# Switch_Line_of_One_DC_Pin.net
KiCad netlist of a schematic drawn in Altium Designer
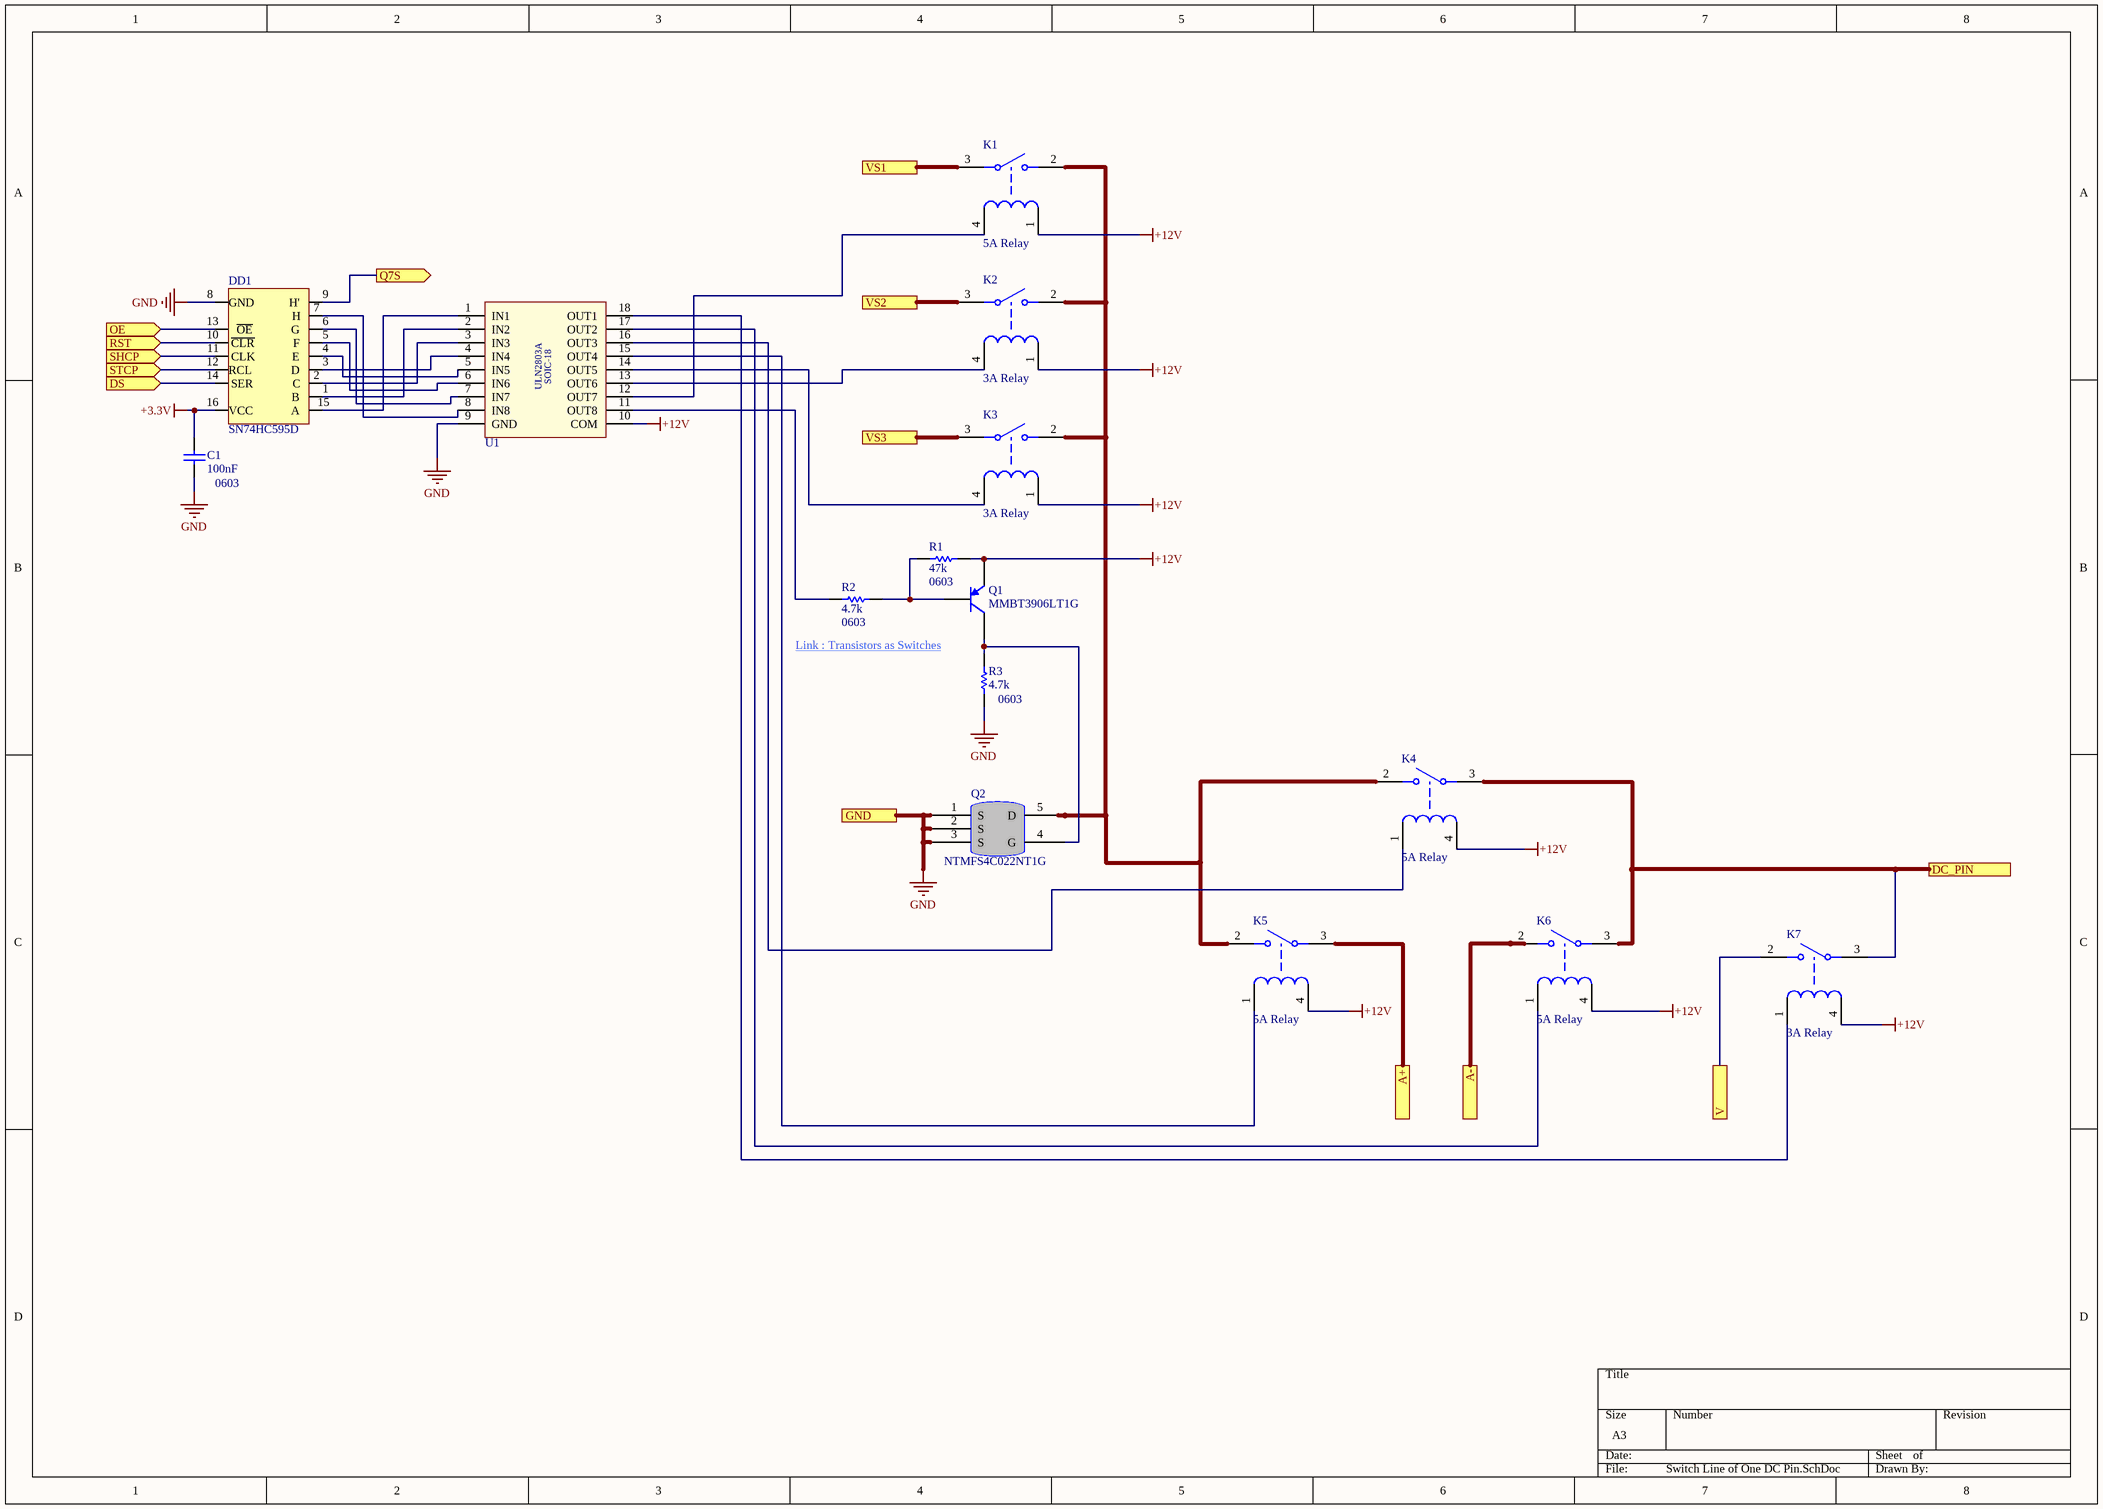
[diagram p0: Switch Line of One DC Pin.SchDoc]

(export (version "E")
  (design (tool "Eeschema 10.0.6"))
  (components
    (comp (ref "C1")
      (value "100nF")
      (footprint "CAPC1608X09N")
      (description "0603 10 nF 50 V ± 10% Tolerance X7R Surface Mount Multilayer Ceramic Capacitor")
      (fields
        (field (name "MANUFACTURE PART NUMBER") "CC0603KRX7R9BB104")
        (field (name "MANUFACTURER") "YAGEO")
        (field (name "PACKAGE / CASE") "0603")
      )
      (libsource (lib "DC Switch Matrix") (part "CMP-2f55e5122ad9f092-5"))
    )
    (comp (ref "DD1")
      (value "SN74HC595D")
      (footprint "PCB-72k1vk0k27b6qyyenbg0-1")
      (description "Shift Register Single 8-Bit Serial to Serial/Parallel 16-Pin SOIC Tube")
      (fields
        (field (name "MANUFACTURE PART NUMBER") "74HC595D,118")
        (field (name "MANUFACTURER") "Nexperia")
      )
      (libsource (lib "DC Switch Matrix") (part "CMP-ded317d957220114-5"))
    )
    (comp (ref "K1")
      (value "5A Relay")
      (footprint "PCB-ei6nokn2irsc2a7yt94x-1")
      (description "General Purpose Non Latching 12VDC SPST-NO 5A Through Hole Relays RoHS")
      (fields
        (field (name "MANUFACTURER") "HF(Xiamen Hongfa Electroacoustic)")
        (field (name "MANUFACTURE PART NUMBER") "HF46F/12-HS1")
      )
      (libsource (lib "DC Switch Matrix") (part "CMP-edc624afa9603201-3"))
    )
    (comp (ref "K2")
      (value "3A Relay")
      (footprint "PCB-ei6nokn2irsc2a7yt94x-1")
      (description "Power Relay 12VDC 3DC/5AAC SPST-NO( (20.5mm 7.2mm 15.3mm)) THT")
      (fields
        (field (name "MANUFACTURER") "Omron Electronics")
        (field (name "MANUFACTURE PART NUMBER") "G5NB-1A-E-DC12")
      )
      (libsource (lib "DC Switch Matrix") (part "CMP-edc624afa9603201-3"))
    )
    (comp (ref "K3")
      (value "3A Relay")
      (footprint "PCB-ei6nokn2irsc2a7yt94x-1")
      (description "Power Relay 12VDC 3DC/5AAC SPST-NO( (20.5mm 7.2mm 15.3mm)) THT")
      (fields
        (field (name "MANUFACTURER") "Omron Electronics")
        (field (name "MANUFACTURE PART NUMBER") "G5NB-1A-E-DC12")
      )
      (libsource (lib "DC Switch Matrix") (part "CMP-edc624afa9603201-3"))
    )
    (comp (ref "K4")
      (value "5A Relay")
      (footprint "PCB-ei6nokn2irsc2a7yt94x-1")
      (description "General Purpose Non Latching 12VDC SPST-NO 5A Through Hole Relays RoHS")
      (fields
        (field (name "MANUFACTURER") "HF(Xiamen Hongfa Electroacoustic)")
        (field (name "MANUFACTURE PART NUMBER") "HF46F/12-HS1")
      )
      (libsource (lib "") (part "CMP-edc624afa9603201-3_1"))
    )
    (comp (ref "K5")
      (value "5A Relay")
      (footprint "PCB-ei6nokn2irsc2a7yt94x-1")
      (description "General Purpose Non Latching 12VDC SPST-NO 5A Through Hole Relays RoHS")
      (fields
        (field (name "MANUFACTURER") "HF(Xiamen Hongfa Electroacoustic)")
        (field (name "MANUFACTURE PART NUMBER") "HF46F/12-HS1")
      )
      (libsource (lib "") (part "CMP-edc624afa9603201-3_1"))
    )
    (comp (ref "K6")
      (value "5A Relay")
      (footprint "PCB-ei6nokn2irsc2a7yt94x-1")
      (description "General Purpose Non Latching 12VDC SPST-NO 5A Through Hole Relays RoHS")
      (fields
        (field (name "MANUFACTURER") "HF(Xiamen Hongfa Electroacoustic)")
        (field (name "MANUFACTURE PART NUMBER") "HF46F/12-HS1")
      )
      (libsource (lib "") (part "CMP-edc624afa9603201-3_1"))
    )
    (comp (ref "K7")
      (value "3A Relay")
      (footprint "PCB-ei6nokn2irsc2a7yt94x-1")
      (description "Power Relay 12VDC 3DC/5AAC SPST-NO( (20.5mm 7.2mm 15.3mm)) THT")
      (fields
        (field (name "MANUFACTURER") "Omron Electronics")
        (field (name "MANUFACTURE PART NUMBER") "G5NB-1A-E-DC12")
      )
      (libsource (lib "") (part "CMP-edc624afa9603201-3_1"))
    )
    (comp (ref "Q1")
      (value "MMBT3906LT1G")
      (footprint "SOT-23")
      (description "Bipolar (BJT) Single Transistor, General Purpose, PNP, -40 V, 250 MHz, 225 mW, -200 mA, 300")
      (fields (field (name "MANUFACTURER") "ON Semiconductor"))
      (libsource (lib "DC Switch Matrix") (part "CMP-857798-9"))
    )
    (comp (ref "Q2")
      (value "NTMFS4C022NT1G")
      (footprint "PCB-iok221h7g3hg093tnixb-1")
      (description "Power MOSFET 30V 136A 1.7 mOhm Single N?Channel SO?8FL")
      (fields (field (name "MANUFACTURER") "ON Semiconductor"))
      (libsource (lib "DC Switch Matrix") (part "CMP-42ac8f2778579d6b-1"))
    )
    (comp (ref "R1")
      (value "47k")
      (footprint "gen0603-2")
      (description "Surface Mount Thick Film Resistor, RC Series, 1 kohm, 100 mW, - 1%, 50 V, 0603 [1608 Metric]")
      (fields
        (field (name "MANUFACTURER") "UNI-ROYAL(Uniroyal Elec)")
        (field (name "MANUFACTURE PART NUMBER") "0603WAF4702T5E")
        (field (name "PACKAGE / CASE") "0603")
      )
      (libsource (lib "DC Switch Matrix") (part "CMP-1853278-27"))
    )
    (comp (ref "R2")
      (value "4.7k")
      (footprint "gen0603-2")
      (description "Surface Mount Thick Film Resistor, RC Series, 1 kohm, 100 mW, - 1%, 50 V, 0603 [1608 Metric]")
      (fields
        (field (name "MANUFACTURER") "YAGEO")
        (field (name "MANUFACTURE PART NUMBER") "RC0603FR-074K7L")
        (field (name "PACKAGE / CASE") "0603")
      )
      (libsource (lib "DC Switch Matrix") (part "CMP-1853278-27"))
    )
    (comp (ref "R3")
      (value "4.7k")
      (footprint "gen0603-2")
      (description "Surface Mount Thick Film Resistor, RC Series, 1 kohm, 100 mW, - 1%, 50 V, 0603 [1608 Metric]")
      (fields
        (field (name "MANUFACTURER") "YAGEO")
        (field (name "MANUFACTURE PART NUMBER") "RC0603FR-074K7L")
        (field (name "PACKAGE / CASE") "0603")
      )
      (libsource (lib "DC Switch Matrix") (part "CMP-1853278-27"))
    )
    (comp (ref "U1")
      (value "ULN2803A (SOIC-18)")
      (footprint "PCB-gcdku7p92m9mz9ih2yin-1")
      (description "Bipolar (BJT) Array Transistor, Darlington, NPN, 50 V, 500 mA, SOIC")
      (fields (field (name "MANUFACTURE PART NUMBER") "ULN2803A") (field (name "MANUFACTURER") "Mixic"))
      (libsource (lib "DC Switch Matrix") (part "CMP-19353911-22"))
    )
  )
  (nets
    (net (code "1") (name "+3.3V") (class "Default")
      (node (ref "C1") (pin "2") (pinfunction "2_2") (pintype "passive"))
      (node (ref "DD1") (pin "16") (pinfunction "VCC_16") (pintype "passive"))
    )
    (net (code "2") (name "+12V") (class "Default")
      (node (ref "K1") (pin "1") (pinfunction "1_1") (pintype "passive"))
      (node (ref "K2") (pin "1") (pinfunction "1_1") (pintype "passive"))
      (node (ref "K3") (pin "1") (pinfunction "1_1") (pintype "passive"))
      (node (ref "K4") (pin "4") (pinfunction "4_4") (pintype "passive"))
      (node (ref "K5") (pin "4") (pinfunction "4_4") (pintype "passive"))
      (node (ref "K6") (pin "4") (pinfunction "4_4") (pintype "passive"))
      (node (ref "K7") (pin "4") (pinfunction "4_4") (pintype "passive"))
      (node (ref "Q1") (pin "2") (pinfunction "E_2") (pintype "passive"))
      (node (ref "R1") (pin "1") (pinfunction "1_1") (pintype "passive"))
      (node (ref "U1") (pin "10") (pinfunction "COM_10") (pintype "power_in"))
    )
    (net (code "3") (name "/A+") (class "Default")
      (node (ref "K5") (pin "3") (pinfunction "3_3") (pintype "passive"))
    )
    (net (code "4") (name "/A-") (class "Default")
      (node (ref "K6") (pin "2") (pinfunction "2_2") (pintype "passive"))
    )
    (net (code "5") (name "/DC_PIN") (class "Default")
      (node (ref "K4") (pin "3") (pinfunction "3_3") (pintype "passive"))
      (node (ref "K6") (pin "3") (pinfunction "3_3") (pintype "passive"))
      (node (ref "K7") (pin "3") (pinfunction "3_3") (pintype "passive"))
    )
    (net (code "6") (name "/DS") (class "Default")
      (node (ref "DD1") (pin "14") (pinfunction "SER_14") (pintype "passive"))
    )
    (net (code "7") (name "/OE") (class "Default")
      (node (ref "DD1") (pin "13") (pinfunction "~{OE}_13") (pintype "passive"))
    )
    (net (code "8") (name "/Q7S") (class "Default")
      (node (ref "DD1") (pin "9") (pinfunction "H'_9") (pintype "passive"))
    )
    (net (code "9") (name "/RST") (class "Default")
      (node (ref "DD1") (pin "10") (pinfunction "~{CLR}_10") (pintype "passive"))
    )
    (net (code "10") (name "/SHCP") (class "Default")
      (node (ref "DD1") (pin "11") (pinfunction "CLK_11") (pintype "passive"))
    )
    (net (code "11") (name "/STCP") (class "Default")
      (node (ref "DD1") (pin "12") (pinfunction "RCL_12") (pintype "passive"))
    )
    (net (code "12") (name "/V") (class "Default")
      (node (ref "K7") (pin "2") (pinfunction "2_2") (pintype "passive"))
    )
    (net (code "13") (name "/VS1") (class "Default")
      (node (ref "K1") (pin "3") (pinfunction "3_3") (pintype "passive"))
    )
    (net (code "14") (name "/VS2") (class "Default")
      (node (ref "K2") (pin "3") (pinfunction "3_3") (pintype "passive"))
    )
    (net (code "15") (name "/VS3") (class "Default")
      (node (ref "K3") (pin "3") (pinfunction "3_3") (pintype "passive"))
    )
    (net (code "16") (name "GND") (class "Default")
      (node (ref "C1") (pin "1") (pinfunction "1_1") (pintype "passive"))
      (node (ref "DD1") (pin "8") (pinfunction "GND_8") (pintype "passive"))
      (node (ref "Q2") (pin "1") (pinfunction "S_1") (pintype "passive"))
      (node (ref "Q2") (pin "2") (pinfunction "S_2") (pintype "passive"))
      (node (ref "Q2") (pin "3") (pinfunction "S_3") (pintype "passive"))
      (node (ref "R3") (pin "1") (pinfunction "1_1") (pintype "passive"))
      (node (ref "U1") (pin "9") (pinfunction "GND_9") (pintype "power_in"))
    )
    (net (code "17") (name "Net-(DD1-A)") (class "Default")
      (node (ref "DD1") (pin "15") (pinfunction "A_15") (pintype "passive"))
      (node (ref "U1") (pin "1") (pinfunction "IN1_1") (pintype "passive"))
    )
    (net (code "18") (name "Net-(DD1-B)") (class "Default")
      (node (ref "DD1") (pin "1") (pinfunction "B_1") (pintype "passive"))
      (node (ref "U1") (pin "2") (pinfunction "IN2_2") (pintype "passive"))
    )
    (net (code "19") (name "Net-(DD1-C)") (class "Default")
      (node (ref "DD1") (pin "2") (pinfunction "C_2") (pintype "passive"))
      (node (ref "U1") (pin "3") (pinfunction "IN3_3") (pintype "passive"))
    )
    (net (code "20") (name "Net-(DD1-D)") (class "Default")
      (node (ref "DD1") (pin "3") (pinfunction "D_3") (pintype "passive"))
      (node (ref "U1") (pin "4") (pinfunction "IN4_4") (pintype "passive"))
    )
    (net (code "21") (name "Net-(DD1-E)") (class "Default")
      (node (ref "DD1") (pin "4") (pinfunction "E_4") (pintype "passive"))
      (node (ref "U1") (pin "5") (pinfunction "IN5_5") (pintype "passive"))
    )
    (net (code "22") (name "Net-(DD1-F)") (class "Default")
      (node (ref "DD1") (pin "5") (pinfunction "F_5") (pintype "passive"))
      (node (ref "U1") (pin "6") (pinfunction "IN6_6") (pintype "passive"))
    )
    (net (code "23") (name "Net-(DD1-G)") (class "Default")
      (node (ref "DD1") (pin "6") (pinfunction "G_6") (pintype "passive"))
      (node (ref "U1") (pin "7") (pinfunction "IN7_7") (pintype "passive"))
    )
    (net (code "24") (name "Net-(DD1-H)") (class "Default")
      (node (ref "DD1") (pin "7") (pinfunction "H_7") (pintype "passive"))
      (node (ref "U1") (pin "8") (pinfunction "IN8_8") (pintype "passive"))
    )
    (net (code "25") (name "Net-(Q1-B)") (class "Default")
      (node (ref "Q1") (pin "1") (pinfunction "B_1") (pintype "passive"))
      (node (ref "R1") (pin "2") (pinfunction "2_2") (pintype "passive"))
      (node (ref "R2") (pin "1") (pinfunction "1_1") (pintype "passive"))
    )
    (net (code "26") (name "Net-(Q1-C)") (class "Default")
      (node (ref "Q1") (pin "3") (pinfunction "C_3") (pintype "passive"))
      (node (ref "Q2") (pin "4") (pinfunction "G_4") (pintype "passive"))
      (node (ref "R3") (pin "2") (pinfunction "2_2") (pintype "passive"))
    )
    (net (code "27") (name "Net-(Q2-D)") (class "Default")
      (node (ref "K1") (pin "2") (pinfunction "2_2") (pintype "passive"))
      (node (ref "K2") (pin "2") (pinfunction "2_2") (pintype "passive"))
      (node (ref "K3") (pin "2") (pinfunction "2_2") (pintype "passive"))
      (node (ref "K4") (pin "2") (pinfunction "2_2") (pintype "passive"))
      (node (ref "K5") (pin "2") (pinfunction "2_2") (pintype "passive"))
      (node (ref "Q2") (pin "5") (pinfunction "D_5") (pintype "passive"))
    )
    (net (code "28") (name "Net-(U1-OUT1)") (class "Default")
      (node (ref "K7") (pin "1") (pinfunction "1_1") (pintype "passive"))
      (node (ref "U1") (pin "18") (pinfunction "OUT1_18") (pintype "power_in"))
    )
    (net (code "29") (name "Net-(U1-OUT2)") (class "Default")
      (node (ref "K6") (pin "1") (pinfunction "1_1") (pintype "passive"))
      (node (ref "U1") (pin "17") (pinfunction "OUT2_17") (pintype "power_in"))
    )
    (net (code "30") (name "Net-(U1-OUT3)") (class "Default")
      (node (ref "K4") (pin "1") (pinfunction "1_1") (pintype "passive"))
      (node (ref "U1") (pin "16") (pinfunction "OUT3_16") (pintype "power_in"))
    )
    (net (code "31") (name "Net-(U1-OUT4)") (class "Default")
      (node (ref "K5") (pin "1") (pinfunction "1_1") (pintype "passive"))
      (node (ref "U1") (pin "15") (pinfunction "OUT4_15") (pintype "power_in"))
    )
    (net (code "32") (name "Net-(U1-OUT5)") (class "Default")
      (node (ref "K3") (pin "4") (pinfunction "4_4") (pintype "passive"))
      (node (ref "U1") (pin "14") (pinfunction "OUT5_14") (pintype "power_in"))
    )
    (net (code "33") (name "Net-(U1-OUT6)") (class "Default")
      (node (ref "K2") (pin "4") (pinfunction "4_4") (pintype "passive"))
      (node (ref "U1") (pin "13") (pinfunction "OUT6_13") (pintype "power_in"))
    )
    (net (code "34") (name "Net-(U1-OUT7)") (class "Default")
      (node (ref "K1") (pin "4") (pinfunction "4_4") (pintype "passive"))
      (node (ref "U1") (pin "12") (pinfunction "OUT7_12") (pintype "power_in"))
    )
    (net (code "35") (name "Net-(U1-OUT8)") (class "Default")
      (node (ref "R2") (pin "2") (pinfunction "2_2") (pintype "passive"))
      (node (ref "U1") (pin "11") (pinfunction "OUT8_11") (pintype "power_in"))
    )
  )
)
